# power_supply.net
KiCad netlist of a schematic drawn in Altium Designer
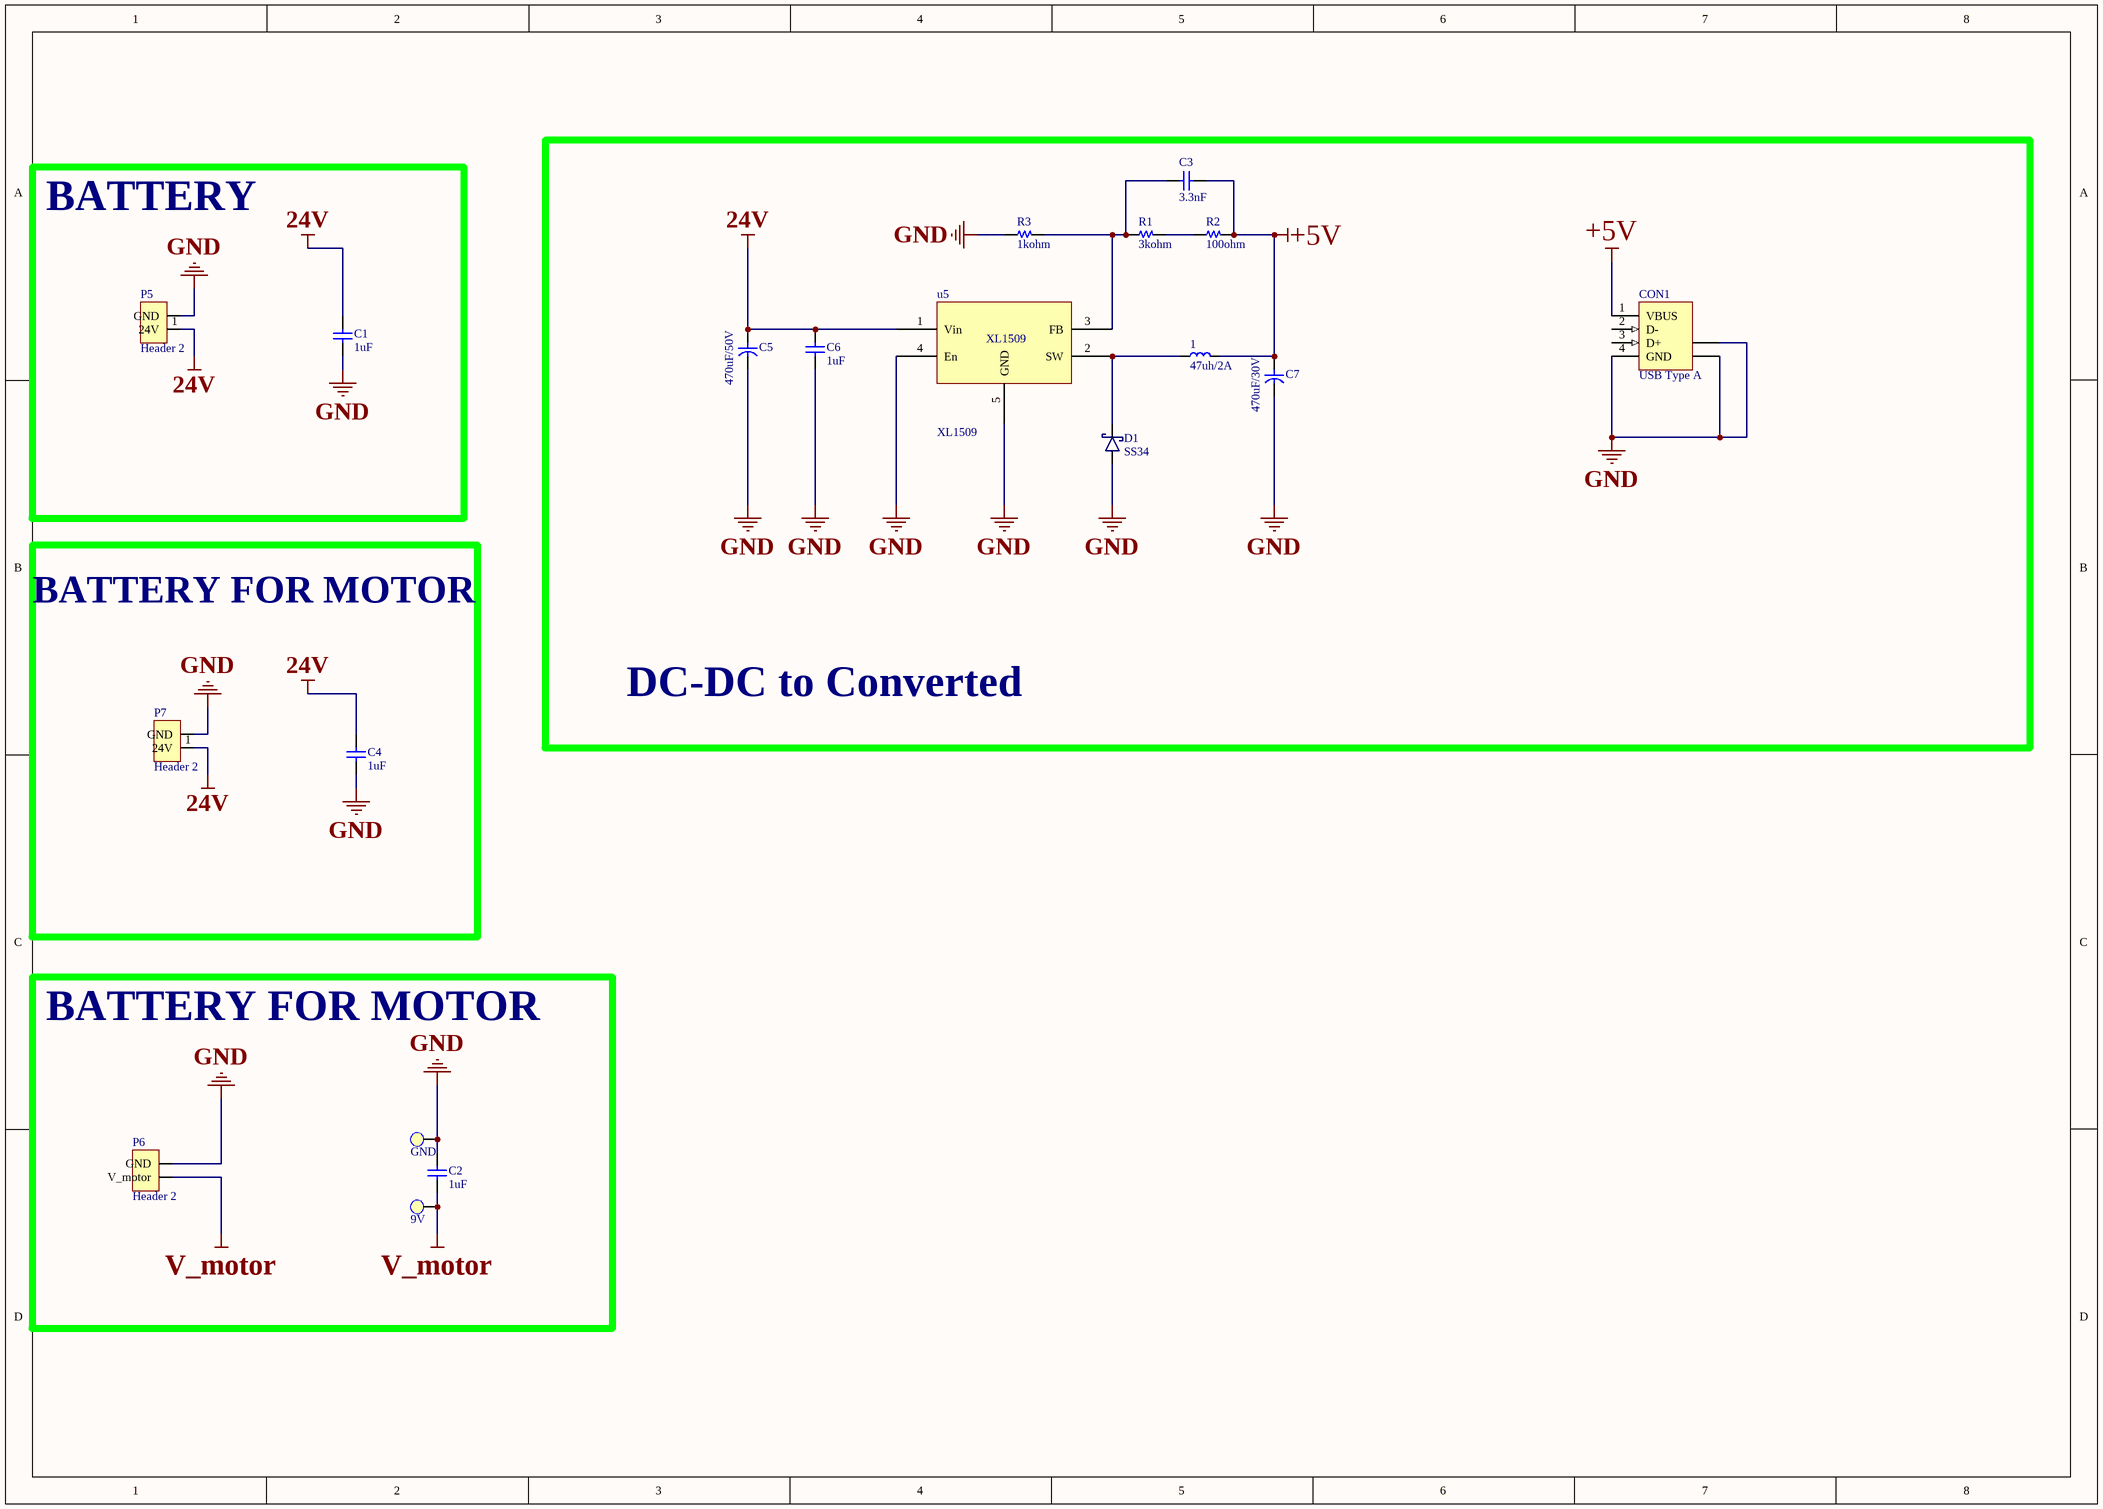
[diagram p0: power_supply.SchDoc]

(export (version "E")
  (design (tool "Eeschema 10.0.6"))
  (components
    (comp (ref "1")
      (value "47uh/2A")
      (footprint "L/D8H10")
      (description "Inductor")
      (libsource (lib "chipfc_libs") (part "Inductor"))
    )
    (comp (ref "C1")
      (value "1uF")
      (footprint "C 0603")
      (description "Capacitor non-pol")
      (libsource (lib "chipfc_libs") (part "Capacitor NP"))
    )
    (comp (ref "C2")
      (value "1uF")
      (footprint "C 0603")
      (description "Capacitor non-pol")
      (libsource (lib "chipfc_libs") (part "Capacitor NP"))
    )
    (comp (ref "C3")
      (value "3.3nF")
      (footprint "C 0805")
      (description "Capacitor non-pol")
      (libsource (lib "chipfc_libs") (part "Capacitor NP"))
    )
    (comp (ref "C4")
      (value "1uF")
      (footprint "C 0603")
      (description "Capacitor non-pol")
      (libsource (lib "chipfc_libs") (part "Capacitor NP"))
    )
    (comp (ref "C5")
      (value "470uF/50V")
      (footprint "CAP/D80/H125/LS30")
      (description "Capacitor pol")
      (libsource (lib "chipfc_libs") (part "Capacitor"))
    )
    (comp (ref "C6")
      (value "1uF")
      (footprint "C 0603")
      (description "Capacitor non-pol")
      (libsource (lib "chipfc_libs") (part "Capacitor NP"))
    )
    (comp (ref "C7")
      (value "470uF/30V")
      (footprint "CAP/D80/H125/LS30")
      (description "Capacitor pol")
      (libsource (lib "chipfc_libs") (part "Capacitor"))
    )
    (comp (ref "CON1")
      (value "USB Type A")
      (footprint "CONN/USB/A/FEMALE/RA")
      (description "USB type A, 4 pins")
      (libsource (lib "connectors") (part "CON USB Type A"))
    )
    (comp (ref "D1")
      (value "SS34")
      (footprint "DIODE_SMA")
      (description "Rectifier Schottky 40V 3A SMA")
      (libsource (lib "Diode") (part "SS34"))
    )
    (comp (ref "GND")
      (value "GND")
      (footprint "TestPoint/SMD/1.5mm")
      (description "Test Point")
      (libsource (lib "chipfc_libs") (part "Test Point"))
    )
    (comp (ref "P5")
      (value "Header 2")
      (footprint "HDR/Header/2/2mm")
      (description "Header, 2-Pin")
      (libsource (lib "connectors") (part "Header 2"))
    )
    (comp (ref "P6")
      (value "Header 2")
      (footprint "HDR/Header/2/2mm")
      (description "Header, 2-Pin")
      (libsource (lib "") (part "Header 2_1"))
    )
    (comp (ref "P7")
      (value "Header 2")
      (footprint "HDR/Header/2/2mm")
      (description "Header, 2-Pin")
      (libsource (lib "connectors") (part "Header 2"))
    )
    (comp (ref "R1")
      (value "3kohm")
      (footprint "R 0805")
      (description "Resistor")
      (libsource (lib "chipfc_libs") (part "Resistor"))
    )
    (comp (ref "R2")
      (value "100ohm")
      (footprint "R 0805")
      (description "Resistor")
      (libsource (lib "chipfc_libs") (part "Resistor"))
    )
    (comp (ref "R3")
      (value "1kohm")
      (footprint "R 0805")
      (description "Resistor")
      (libsource (lib "chipfc_libs") (part "Resistor"))
    )
    (comp (ref "u5") (value "XL1509") (footprint "SO8") (libsource (lib "Library") (part "XL1509")))
    (comp (ref "V_MOTOR")
      (value "9V")
      (footprint "TestPoint/SMD/1.5mm")
      (description "Test Point")
      (libsource (lib "chipfc_libs") (part "Test Point"))
    )
  )
  (nets
    (net (code "1") (name "+5V") (class "Default")
      (node (ref "1") (pin "2") (pinfunction "2_2") (pintype "passive"))
      (node (ref "C3") (pin "2") (pinfunction "2_2") (pintype "passive"))
      (node (ref "C7") (pin "1") (pinfunction "1_1") (pintype "passive"))
      (node (ref "CON1") (pin "1") (pinfunction "VBUS_1") (pintype "power_in"))
      (node (ref "R2") (pin "2") (pinfunction "2_2") (pintype "passive"))
    )
    (net (code "2") (name "24V") (class "Default")
      (node (ref "C1") (pin "1") (pinfunction "1_1") (pintype "passive"))
      (node (ref "C4") (pin "1") (pinfunction "1_1") (pintype "passive"))
      (node (ref "C5") (pin "1") (pinfunction "1_1") (pintype "passive"))
      (node (ref "C6") (pin "1") (pinfunction "1_1") (pintype "passive"))
      (node (ref "P5") (pin "1") (pinfunction "24V_1") (pintype "passive"))
      (node (ref "P7") (pin "1") (pinfunction "24V_1") (pintype "passive"))
      (node (ref "u5") (pin "1") (pinfunction "Vin_1") (pintype "passive"))
    )
    (net (code "3") (name "GND") (class "Default")
      (node (ref "C1") (pin "2") (pinfunction "2_2") (pintype "passive"))
      (node (ref "C2") (pin "1") (pinfunction "1_1") (pintype "passive"))
      (node (ref "C4") (pin "2") (pinfunction "2_2") (pintype "passive"))
      (node (ref "C5") (pin "2") (pinfunction "2_2") (pintype "passive"))
      (node (ref "C6") (pin "2") (pinfunction "2_2") (pintype "passive"))
      (node (ref "C7") (pin "2") (pinfunction "2_2") (pintype "passive"))
      (node (ref "CON1") (pin "4") (pinfunction "GND_4") (pintype "power_in"))
      (node (ref "CON1") (pin "5") (pinfunction "SHLD_5") (pintype "passive"))
      (node (ref "CON1") (pin "6") (pinfunction "SHLD_6") (pintype "passive"))
      (node (ref "D1") (pin "1") (pinfunction "1_1") (pintype "passive"))
      (node (ref "GND") (pin "1") (pinfunction "TP_1") (pintype "passive"))
      (node (ref "P5") (pin "2") (pinfunction "GND_2") (pintype "passive"))
      (node (ref "P6") (pin "2") (pinfunction "GND_2") (pintype "passive"))
      (node (ref "P7") (pin "2") (pinfunction "GND_2") (pintype "passive"))
      (node (ref "R3") (pin "1") (pinfunction "1_1") (pintype "passive"))
      (node (ref "u5") (pin "4") (pinfunction "En_4") (pintype "passive"))
      (node (ref "u5") (pin "5") (pinfunction "GND_5") (pintype "passive"))
    )
    (net (code "4") (name "Net-(R1-Pad2)") (class "Default")
      (node (ref "R1") (pin "2") (pinfunction "2_2") (pintype "passive"))
      (node (ref "R2") (pin "1") (pinfunction "1_1") (pintype "passive"))
    )
    (net (code "5") (name "Net-(u5-FB)") (class "Default")
      (node (ref "C3") (pin "1") (pinfunction "1_1") (pintype "passive"))
      (node (ref "R1") (pin "1") (pinfunction "1_1") (pintype "passive"))
      (node (ref "R3") (pin "2") (pinfunction "2_2") (pintype "passive"))
      (node (ref "u5") (pin "3") (pinfunction "FB_3") (pintype "passive"))
    )
    (net (code "6") (name "Net-(u5-SW)") (class "Default")
      (node (ref "1") (pin "1") (pinfunction "1_1") (pintype "passive"))
      (node (ref "D1") (pin "2") (pintype "passive"))
      (node (ref "u5") (pin "2") (pinfunction "SW_2") (pintype "passive"))
    )
    (net (code "7") (name "V_motor") (class "Default")
      (node (ref "C2") (pin "2") (pinfunction "2_2") (pintype "passive"))
      (node (ref "P6") (pin "1") (pinfunction "V_motor_1") (pintype "passive"))
      (node (ref "V_MOTOR") (pin "1") (pinfunction "TP_1") (pintype "passive"))
    )
    (net (code "8") (name "unconnected-(CON1-D+-Pad3)") (class "Default")
      (node (ref "CON1") (pin "3") (pinfunction "D+_3") (pintype "input"))
    )
    (net (code "9") (name "unconnected-(CON1-D--Pad2)") (class "Default")
      (node (ref "CON1") (pin "2") (pinfunction "D-_2") (pintype "input"))
    )
  )
)
